# senseBox-Expander_v20.net
KiCad netlist of a schematic drawn in EAGLE
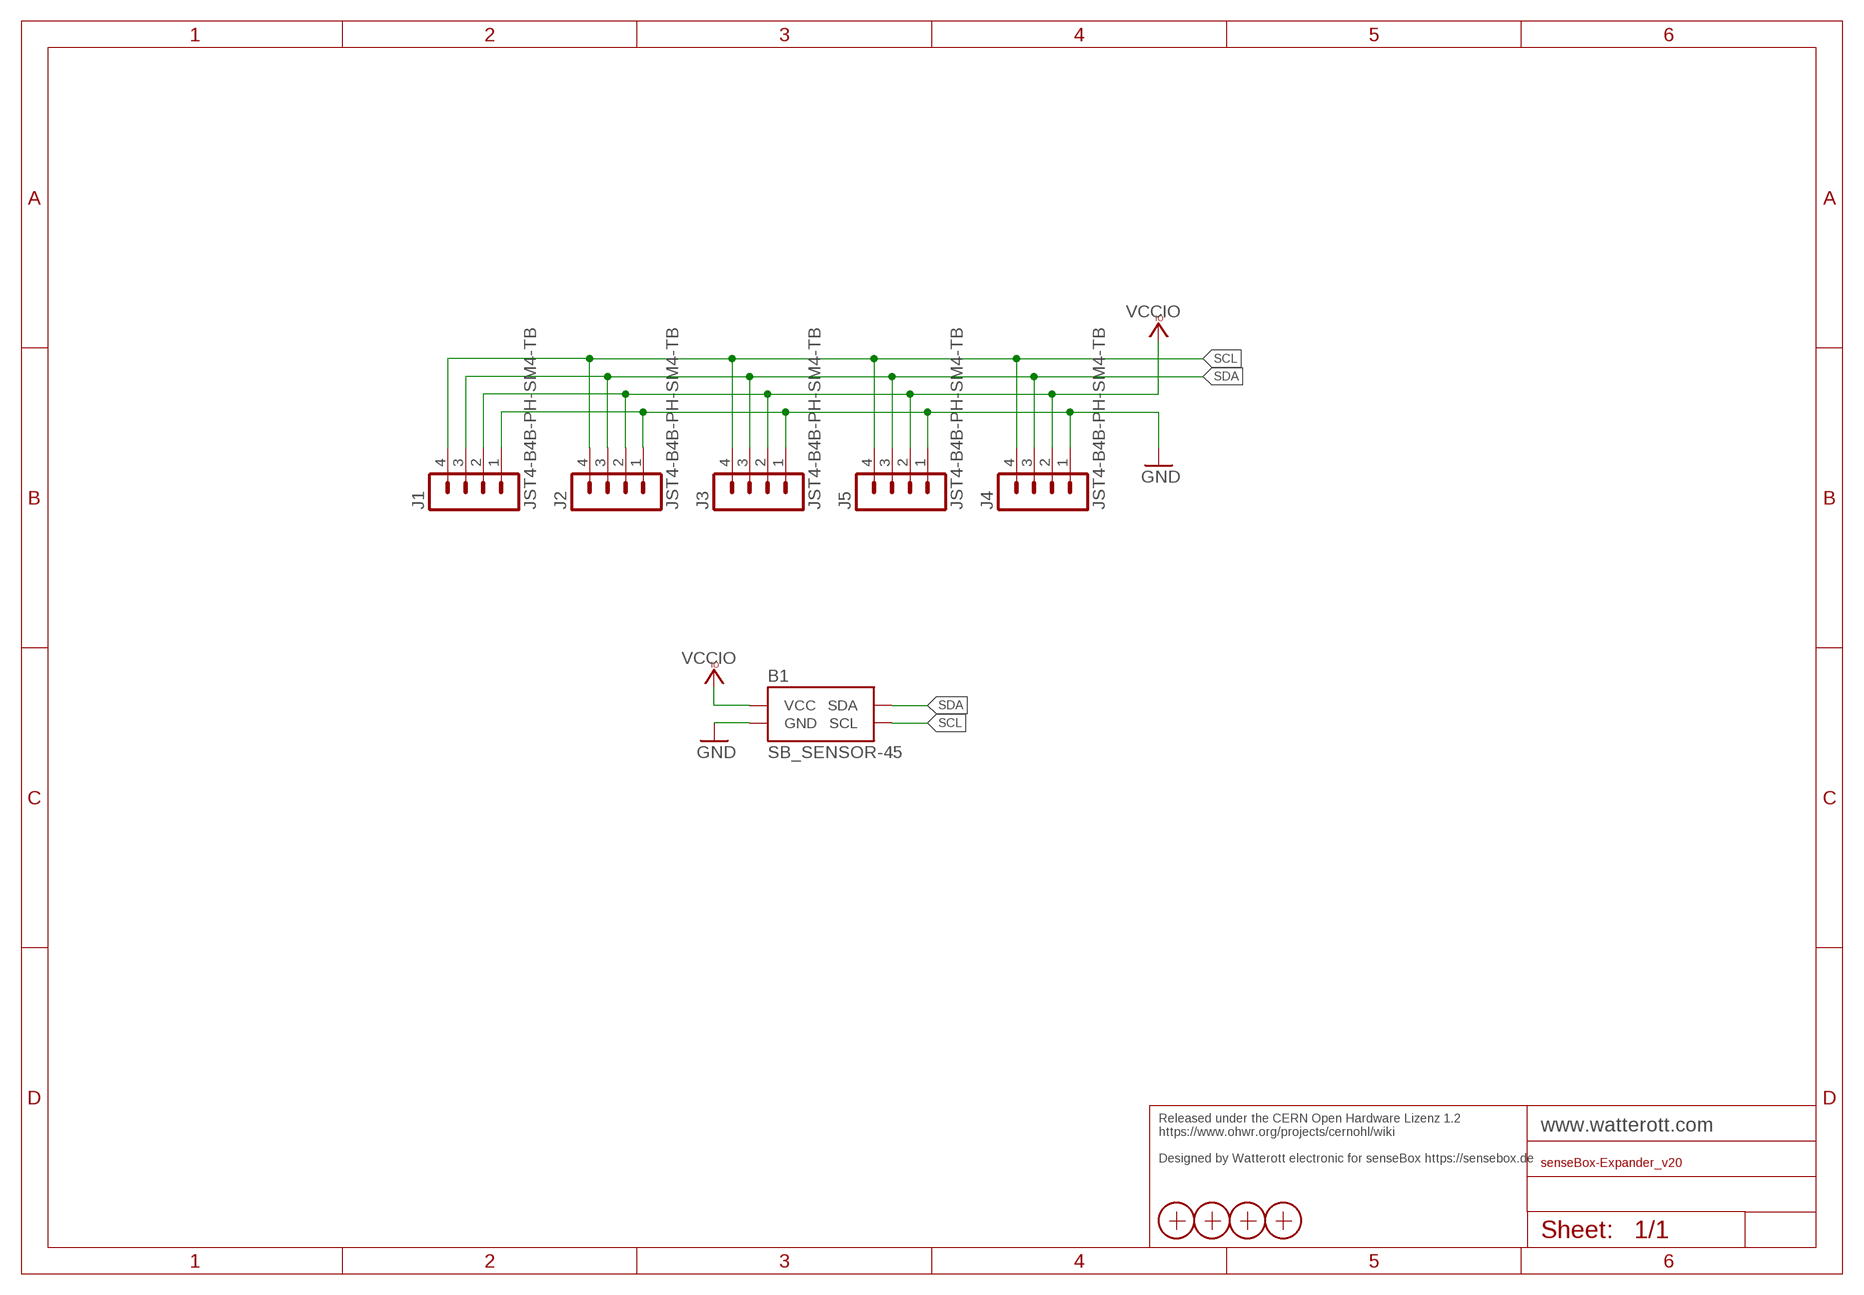
[diagram p0: schematic, sheet 1]

(export (version "E")
  (design (tool "Eeschema 10.0.6"))
  (components
    (comp (ref "B1")
      (value "SB_SENSOR-45")
      (footprint "eagle-import:SB-45X25")
      (libsource (lib "eagle-import") (part "SB_SENSOR-45"))
    )
    (comp (ref "J1")
      (value "JST4-B4B-PH-SM4-TB")
      (footprint "eagle-import:JST_B4B-PH-SM4-TB")
      (libsource (lib "eagle-import") (part "JST4-B4B-PH-SM4-TB"))
    )
    (comp (ref "J2")
      (value "JST4-B4B-PH-SM4-TB")
      (footprint "eagle-import:JST_B4B-PH-SM4-TB")
      (libsource (lib "eagle-import") (part "JST4-B4B-PH-SM4-TB"))
    )
    (comp (ref "J3")
      (value "JST4-B4B-PH-SM4-TB")
      (footprint "eagle-import:JST_B4B-PH-SM4-TB")
      (libsource (lib "eagle-import") (part "JST4-B4B-PH-SM4-TB"))
    )
    (comp (ref "J4")
      (value "JST4-B4B-PH-SM4-TB")
      (footprint "eagle-import:JST_B4B-PH-SM4-TB")
      (libsource (lib "eagle-import") (part "JST4-B4B-PH-SM4-TB"))
    )
    (comp (ref "J5")
      (value "JST4-B4B-PH-SM4-TB")
      (footprint "eagle-import:JST_B4B-PH-SM4-TB")
      (libsource (lib "eagle-import") (part "JST4-B4B-PH-SM4-TB"))
    )
    (comp (ref "X1")
      (value "PASSER-07")
      (footprint "eagle-import:PASSER_07MM")
      (libsource (lib "eagle-import") (part "PASSER-07"))
    )
    (comp (ref "X2")
      (value "PASSER-07")
      (footprint "eagle-import:PASSER_07MM")
      (libsource (lib "eagle-import") (part "PASSER-07"))
    )
    (comp (ref "X3")
      (value "PASSER-07")
      (footprint "eagle-import:PASSER_07MM")
      (libsource (lib "eagle-import") (part "PASSER-07"))
    )
    (comp (ref "X4")
      (value "PASSER-07")
      (footprint "eagle-import:PASSER_07MM")
      (libsource (lib "eagle-import") (part "PASSER-07"))
    )
  )
  (nets
    (net (code "1") (name "GND") (class "Default")
      (node (ref "B1") (pin "GND") (pinfunction "GND_GND") (pintype "power_in"))
      (node (ref "J1") (pin "1") (pinfunction "1_1") (pintype "passive"))
      (node (ref "J2") (pin "1") (pinfunction "1_1") (pintype "passive"))
      (node (ref "J3") (pin "1") (pinfunction "1_1") (pintype "passive"))
      (node (ref "J4") (pin "1") (pinfunction "1_1") (pintype "passive"))
      (node (ref "J5") (pin "1") (pinfunction "1_1") (pintype "passive"))
    )
    (net (code "2") (name "SCL") (class "Default")
      (node (ref "B1") (pin "SCL") (pinfunction "SCL_SCL") (pintype "bidirectional"))
      (node (ref "J1") (pin "4") (pinfunction "4_4") (pintype "passive"))
      (node (ref "J2") (pin "4") (pinfunction "4_4") (pintype "passive"))
      (node (ref "J3") (pin "4") (pinfunction "4_4") (pintype "passive"))
      (node (ref "J4") (pin "4") (pinfunction "4_4") (pintype "passive"))
      (node (ref "J5") (pin "4") (pinfunction "4_4") (pintype "passive"))
    )
    (net (code "3") (name "SDA") (class "Default")
      (node (ref "B1") (pin "SDA") (pinfunction "SDA_SDA") (pintype "bidirectional"))
      (node (ref "J1") (pin "3") (pinfunction "3_3") (pintype "passive"))
      (node (ref "J2") (pin "3") (pinfunction "3_3") (pintype "passive"))
      (node (ref "J3") (pin "3") (pinfunction "3_3") (pintype "passive"))
      (node (ref "J4") (pin "3") (pinfunction "3_3") (pintype "passive"))
      (node (ref "J5") (pin "3") (pinfunction "3_3") (pintype "passive"))
    )
    (net (code "4") (name "VCCIO") (class "Default")
      (node (ref "B1") (pin "VCC") (pinfunction "VCC_VCC") (pintype "power_in"))
      (node (ref "J1") (pin "2") (pinfunction "2_2") (pintype "passive"))
      (node (ref "J2") (pin "2") (pinfunction "2_2") (pintype "passive"))
      (node (ref "J3") (pin "2") (pinfunction "2_2") (pintype "passive"))
      (node (ref "J4") (pin "2") (pinfunction "2_2") (pintype "passive"))
      (node (ref "J5") (pin "2") (pinfunction "2_2") (pintype "passive"))
    )
  )
)
